# usb-2_0-current-probe.net
KiCad netlist of a schematic drawn in EAGLE
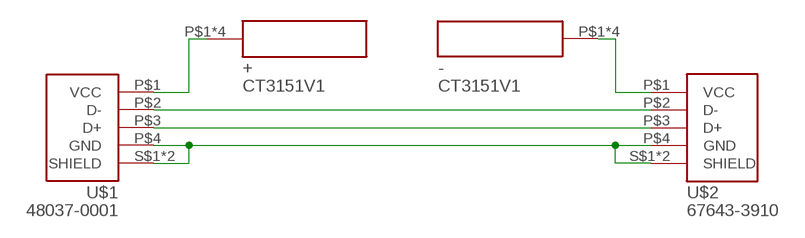
[diagram p0: schematic, sheet 1]

(export (version "E")
  (design (tool "Eeschema 10.0.6"))
  (components
    (comp (ref "+")
      (value "CT3151V1")
      (footprint "eagle-import:CT3151V1")
      (libsource (lib "eagle-import") (part "CT3151V1"))
    )
    (comp (ref "-")
      (value "CT3151V1")
      (footprint "eagle-import:CT3151V1")
      (libsource (lib "eagle-import") (part "CT3151V1"))
    )
    (comp (ref "U$1")
      (value "48037-0001")
      (footprint "eagle-import:48037-0001")
      (libsource (lib "eagle-import") (part "48037-0001"))
    )
    (comp (ref "U$2")
      (value "67643-3910")
      (footprint "eagle-import:67643-3910")
      (libsource (lib "eagle-import") (part "67643-3910"))
    )
  )
  (nets
    (net (code "1") (name "Net-(U$1-D+)") (class "Default")
      (node (ref "U$1") (pin "P$3") (pinfunction "D+_P$3") (pintype "bidirectional"))
      (node (ref "U$2") (pin "P$3") (pinfunction "D+_P$3") (pintype "bidirectional"))
    )
    (net (code "2") (name "Net-(U$1-D-)") (class "Default")
      (node (ref "U$1") (pin "P$2") (pinfunction "D-_P$2") (pintype "bidirectional"))
      (node (ref "U$2") (pin "P$2") (pinfunction "D-_P$2") (pintype "bidirectional"))
    )
    (net (code "3") (name "Net-(U$1-GND)") (class "Default")
      (node (ref "U$1") (pin "P$4") (pinfunction "GND_P$4") (pintype "bidirectional"))
      (node (ref "U$1") (pin "S$1") (pinfunction "SHIELD_S$1") (pintype "bidirectional"))
      (node (ref "U$1") (pin "S$2") (pinfunction "SHIELD_S$2") (pintype "bidirectional"))
      (node (ref "U$2") (pin "P$4") (pinfunction "GND_P$4") (pintype "bidirectional"))
      (node (ref "U$2") (pin "S$1") (pinfunction "SHIELD_S$1") (pintype "bidirectional"))
      (node (ref "U$2") (pin "S$2") (pinfunction "SHIELD_S$2") (pintype "bidirectional"))
    )
    (net (code "4") (name "Net-(U$1-VCC)") (class "Default")
      (node (ref "+") (pin "P$1") (pinfunction "P$1_P$1") (pintype "bidirectional"))
      (node (ref "+") (pin "P$2") (pinfunction "P$1_P$2") (pintype "bidirectional"))
      (node (ref "+") (pin "P$3") (pinfunction "P$1_P$3") (pintype "bidirectional"))
      (node (ref "+") (pin "P$4") (pinfunction "P$1_P$4") (pintype "bidirectional"))
      (node (ref "U$1") (pin "P$1") (pinfunction "VCC_P$1") (pintype "bidirectional"))
    )
    (net (code "5") (name "Net-(U$2-VCC)") (class "Default")
      (node (ref "-") (pin "P$1") (pinfunction "P$1_P$1") (pintype "bidirectional"))
      (node (ref "-") (pin "P$2") (pinfunction "P$1_P$2") (pintype "bidirectional"))
      (node (ref "-") (pin "P$3") (pinfunction "P$1_P$3") (pintype "bidirectional"))
      (node (ref "-") (pin "P$4") (pinfunction "P$1_P$4") (pintype "bidirectional"))
      (node (ref "U$2") (pin "P$1") (pinfunction "VCC_P$1") (pintype "bidirectional"))
    )
  )
)
